# RTC.net
KiCad netlist of a schematic drawn in Altium Designer
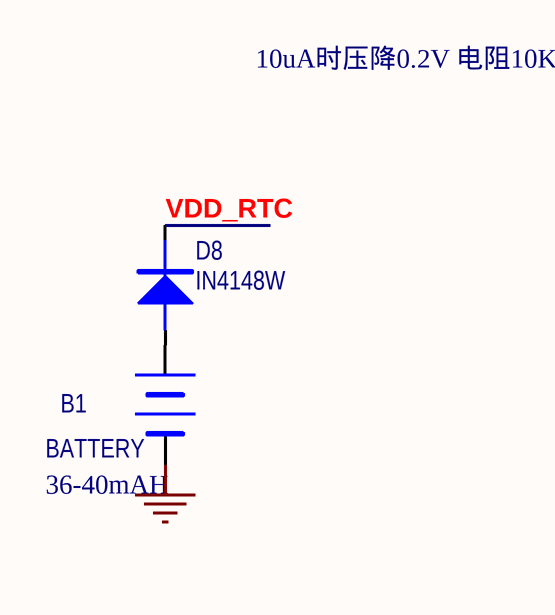
[diagram p0: RTC.SchDoc]

(export (version "E")
  (design (tool "Eeschema 10.0.6"))
  (components
    (comp (ref "B1")
      (value "BATTERY")
      (footprint "BR2032-1GV")
      (description "电池座")
      (fields (field (name "VOLUME") "36-40mAH"))
      (libsource (lib "*") (part "BATTERY"))
    )
    (comp (ref "D8")
      (value "IN4148W")
      (footprint "SOD123")
      (description "DIODE")
      (libsource (lib "*") (part "DIODE"))
    )
  )
  (nets
    (net (code "1") (name "/VDD_RTC") (class "Default")
      (node (ref "D8") (pin "2") (pinfunction "2_2") (pintype "passive"))
    )
    (net (code "2") (name "GND") (class "Default") (node (ref "B1") (pin "2") (pintype "passive")))
    (net (code "3") (name "Net-(B1-Pad1)") (class "Default")
      (node (ref "B1") (pin "1") (pintype "passive"))
      (node (ref "D8") (pin "1") (pinfunction "1_1") (pintype "passive"))
    )
  )
)
